# Pasa_Altos.net
KiCad netlist of a schematic drawn in Altium Designer
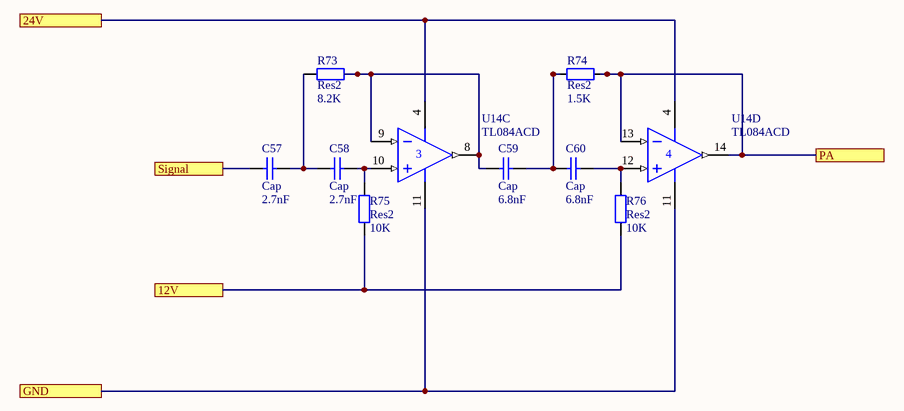
[diagram p0: Pasa Altos.SchDoc]

(export (version "E")
  (design (tool "Eeschema 10.0.6"))
  (components
    (comp (ref "C57")
      (value "Cap")
      (footprint "rad-0.2")
      (description "Capacitor")
      (fields (field (name "ALTIUM_VALUE") "2.7nF") (field (name "PUBLISHER") "Altium Limited"))
      (libsource (lib "Miscellaneous Devices") (part "Cap"))
    )
    (comp (ref "C58")
      (value "Cap")
      (footprint "rad-0.2")
      (description "Capacitor")
      (fields (field (name "ALTIUM_VALUE") "2.7nF") (field (name "PUBLISHER") "Altium Limited"))
      (libsource (lib "Miscellaneous Devices") (part "Cap"))
    )
    (comp (ref "C59")
      (value "Cap")
      (footprint "rad-0.2")
      (description "Capacitor")
      (fields (field (name "ALTIUM_VALUE") "6.8nF") (field (name "PUBLISHER") "Altium Limited"))
      (libsource (lib "Miscellaneous Devices") (part "Cap"))
    )
    (comp (ref "C60")
      (value "Cap")
      (footprint "rad-0.2")
      (description "Capacitor")
      (fields (field (name "ALTIUM_VALUE") "6.8nF") (field (name "PUBLISHER") "Altium Limited"))
      (libsource (lib "Miscellaneous Devices") (part "Cap"))
    )
    (comp (ref "R73")
      (value "Res2")
      (footprint "1206 resistor")
      (description "Resistor")
      (fields (field (name "ALTIUM_VALUE") "8.2K") (field (name "PUBLISHER") "Altium Limited"))
      (libsource (lib "") (part "Res2_1"))
    )
    (comp (ref "R74")
      (value "Res2")
      (footprint "1206 resistor")
      (description "Resistor")
      (fields (field (name "ALTIUM_VALUE") "1.5K") (field (name "PUBLISHER") "Altium Limited"))
      (libsource (lib "") (part "Res2_1"))
    )
    (comp (ref "R75")
      (value "Res2")
      (footprint "1206 resistor")
      (description "Resistor")
      (fields (field (name "ALTIUM_VALUE") "10K") (field (name "PUBLISHER") "Altium Limited"))
      (libsource (lib "Miscellaneous Devices") (part "Res2"))
    )
    (comp (ref "R76")
      (value "Res2")
      (footprint "1206 resistor")
      (description "Resistor")
      (fields (field (name "ALTIUM_VALUE") "10K") (field (name "PUBLISHER") "Altium Limited"))
      (libsource (lib "Miscellaneous Devices") (part "Res2"))
    )
    (comp (ref "U14")
      (value "TL084ACD")
      (footprint "751A-02_N")
      (description "JFET-Input Operational Amplifier")
      (fields (field (name "PUBLISHER") "Altium Limited"))
      (libsource (lib "Motorola Amplifier Operational Amplifier") (part "TL084ACD"))
    )
  )
  (nets
    (net (code "1") (name "/12V") (class "Default")
      (node (ref "R75") (pin "1") (pinfunction "1_1") (pintype "passive"))
      (node (ref "R76") (pin "1") (pinfunction "1_1") (pintype "passive"))
    )
    (net (code "2") (name "/24V") (class "Default")
      (node (ref "U14") (pin "4") (pinfunction "V+_4") (pintype "power_in"))
    )
    (net (code "3") (name "/GND") (class "Default")
      (node (ref "U14") (pin "11") (pinfunction "V-_11") (pintype "power_in"))
    )
    (net (code "4") (name "/PA") (class "Default")
      (node (ref "R74") (pin "2") (pinfunction "2_2") (pintype "passive"))
      (node (ref "U14") (pin "13") (pinfunction "IN-_13") (pintype "input"))
      (node (ref "U14") (pin "14") (pinfunction "OUT_14") (pintype "output"))
    )
    (net (code "5") (name "/Signal") (class "Default")
      (node (ref "C57") (pin "2") (pinfunction "2_2") (pintype "passive"))
    )
    (net (code "6") (name "Net-(C57-Pad1)") (class "Default")
      (node (ref "C57") (pin "1") (pinfunction "1_1") (pintype "passive"))
      (node (ref "C58") (pin "2") (pinfunction "2_2") (pintype "passive"))
      (node (ref "R73") (pin "1") (pinfunction "1_1") (pintype "passive"))
    )
    (net (code "7") (name "Net-(C59-Pad1)") (class "Default")
      (node (ref "C59") (pin "1") (pinfunction "1_1") (pintype "passive"))
      (node (ref "C60") (pin "2") (pinfunction "2_2") (pintype "passive"))
      (node (ref "R74") (pin "1") (pinfunction "1_1") (pintype "passive"))
    )
    (net (code "8") (name "Net-(U14C-IN+)") (class "Default")
      (node (ref "C58") (pin "1") (pinfunction "1_1") (pintype "passive"))
      (node (ref "R75") (pin "2") (pinfunction "2_2") (pintype "passive"))
      (node (ref "U14") (pin "10") (pinfunction "IN+_10") (pintype "input"))
    )
    (net (code "9") (name "Net-(U14C-IN-)") (class "Default")
      (node (ref "C59") (pin "2") (pinfunction "2_2") (pintype "passive"))
      (node (ref "R73") (pin "2") (pinfunction "2_2") (pintype "passive"))
      (node (ref "U14") (pin "8") (pinfunction "OUT_8") (pintype "output"))
      (node (ref "U14") (pin "9") (pinfunction "IN-_9") (pintype "input"))
    )
    (net (code "10") (name "Net-(U14D-IN+)") (class "Default")
      (node (ref "C60") (pin "1") (pinfunction "1_1") (pintype "passive"))
      (node (ref "R76") (pin "2") (pinfunction "2_2") (pintype "passive"))
      (node (ref "U14") (pin "12") (pinfunction "IN+_12") (pintype "input"))
    )
  )
)
